# andres-rgb-controller-esp8266-12_2021-06.net
KiCad netlist of a schematic drawn in EasyEDA
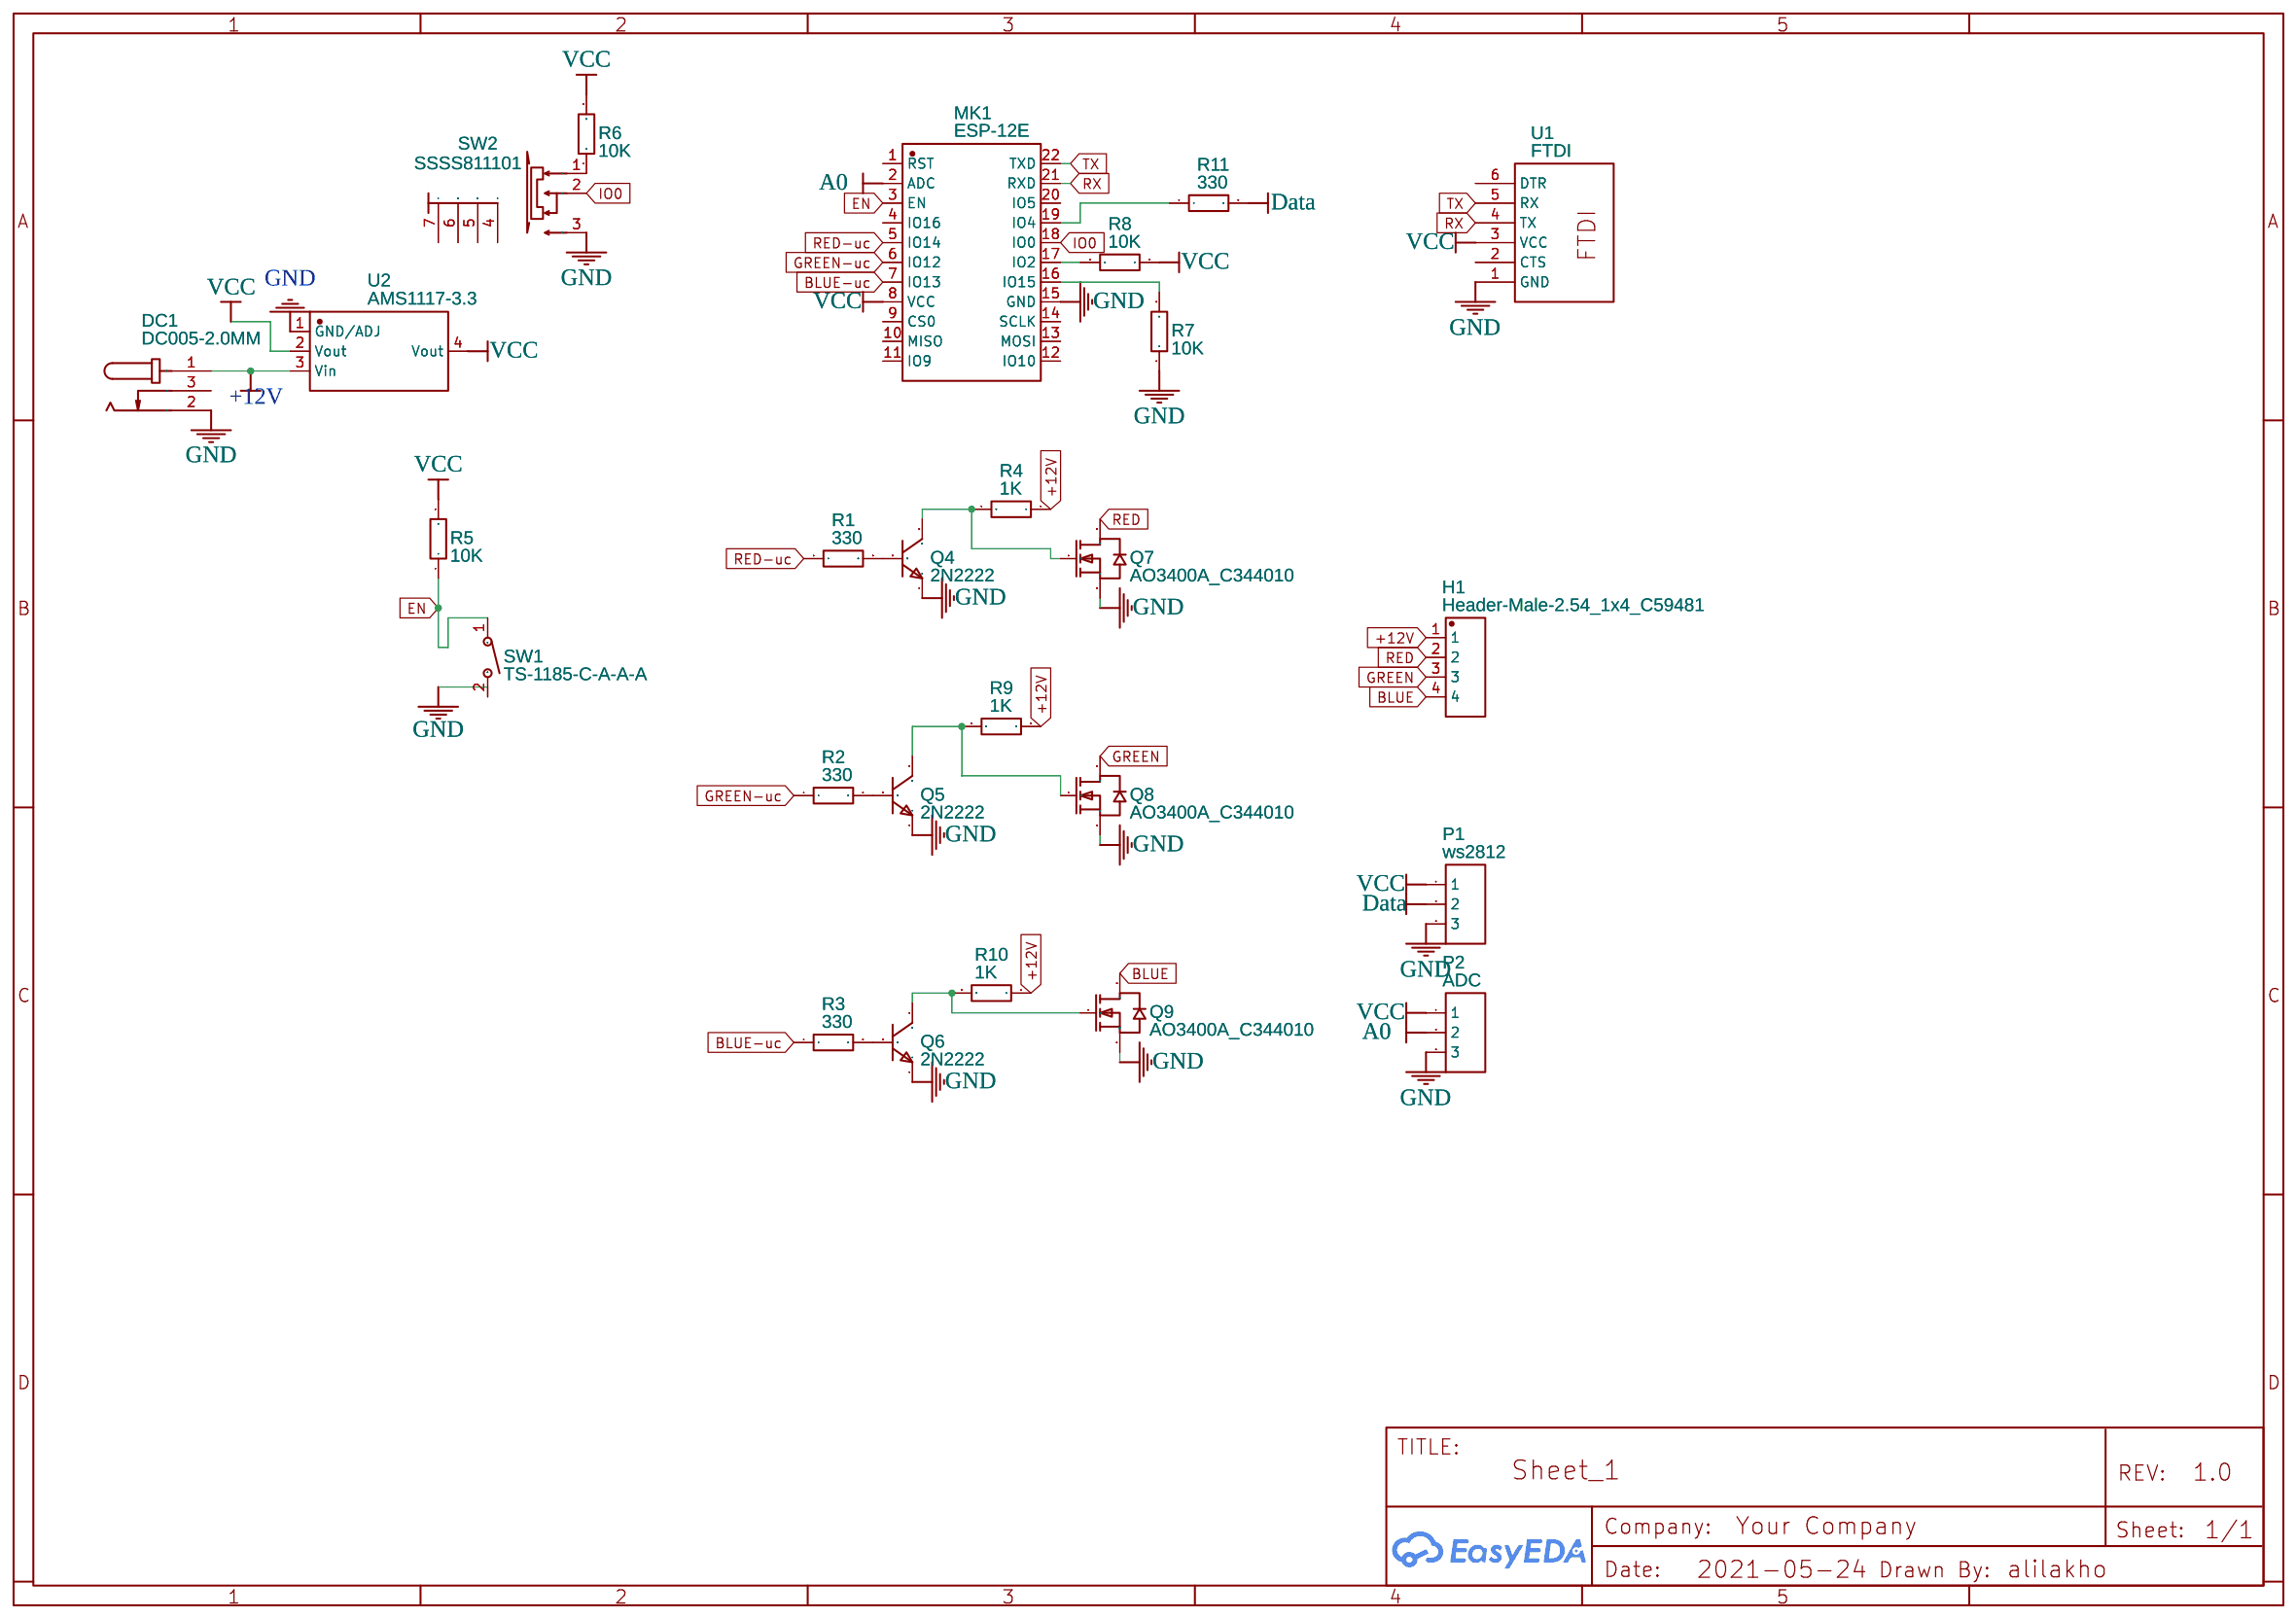
[diagram p0: schematic sheet]

(export (version "E")
  (design (tool "Eeschema 10.0.6"))
  (components
    (comp (ref "DC1")
      (value "DC005-2.0MM")
      (fields (field (name "BOM_Supplier Part") "C111567"))
      (libsource (lib "") (part "DC005-2.0MM"))
    )
    (comp (ref "H1")
      (value "Header-Male-2.54_1x4_C59481")
      (fields
        (field (name "BOM_Manufacturer Part") "Headers  Pins 1*4P")
        (field (name "BOM_Supplier Part") "C59481")
      )
      (libsource (lib "") (part "Header-Male-2.54_1x4_C59481"))
    )
    (comp (ref "MK1")
      (value "ESP-12E")
      (fields (field (name "BOM_Supplier Part") "C89297"))
      (libsource (lib "") (part "ESP-12E"))
    )
    (comp (ref "P1")
      (value "ws2812")
      (fields
        (field (name "BOM_Manufacturer Part") "Header-Female-2.54_1x3")
        (field (name "BOM_Supplier Part") "C146243")
      )
      (libsource (lib "") (part "Header-Female-2.54_1x3"))
    )
    (comp (ref "P2")
      (value "ADC")
      (fields
        (field (name "BOM_Manufacturer Part") "Header-Female-2.54_1x3")
        (field (name "BOM_Supplier Part") "C146243")
      )
      (libsource (lib "") (part "Header-Female-2.54_1x3"))
    )
    (comp (ref "Q4")
      (value "2N2222")
      (fields (field (name "BOM_Supplier Part") "C118536"))
      (libsource (lib "") (part "2N2222"))
    )
    (comp (ref "Q5")
      (value "2N2222")
      (fields (field (name "BOM_Supplier Part") "C118536"))
      (libsource (lib "") (part "2N2222"))
    )
    (comp (ref "Q6")
      (value "2N2222")
      (fields (field (name "BOM_Supplier Part") "C118536"))
      (libsource (lib "") (part "2N2222"))
    )
    (comp (ref "Q7")
      (value "AO3400A_C344010")
      (fields (field (name "BOM_Manufacturer Part") "AO3400A") (field (name "BOM_Supplier Part") "C344010"))
      (libsource (lib "") (part "AO3400A_C344010"))
    )
    (comp (ref "Q8")
      (value "AO3400A_C344010")
      (fields (field (name "BOM_Manufacturer Part") "AO3400A") (field (name "BOM_Supplier Part") "C344010"))
      (libsource (lib "") (part "AO3400A_C344010"))
    )
    (comp (ref "Q9")
      (value "AO3400A_C344010")
      (fields (field (name "BOM_Manufacturer Part") "AO3400A") (field (name "BOM_Supplier Part") "C344010"))
      (libsource (lib "") (part "AO3400A_C344010"))
    )
    (comp (ref "R1")
      (value "330")
      (fields
        (field (name "BOM_Manufacturer Part") "0805W8J0331T5E")
        (field (name "BOM_Supplier Part") "C25306")
      )
      (libsource (lib "") (part "0805W8J0331T5E"))
    )
    (comp (ref "R2")
      (value "330")
      (fields
        (field (name "BOM_Manufacturer Part") "0805W8J0331T5E")
        (field (name "BOM_Supplier Part") "C25306")
      )
      (libsource (lib "") (part "0805W8J0331T5E"))
    )
    (comp (ref "R3")
      (value "330")
      (fields
        (field (name "BOM_Manufacturer Part") "0805W8J0331T5E")
        (field (name "BOM_Supplier Part") "C25306")
      )
      (libsource (lib "") (part "0805W8J0331T5E"))
    )
    (comp (ref "R4")
      (value "1K")
      (fields
        (field (name "BOM_Manufacturer Part") "1210W3J0102T5E")
        (field (name "BOM_Supplier Part") "C25681")
      )
      (libsource (lib "") (part "1210W3J0102T5E"))
    )
    (comp (ref "R5")
      (value "10K")
      (fields
        (field (name "BOM_Manufacturer Part") "1206W4F1002T5E")
        (field (name "BOM_Supplier Part") "C17902")
      )
      (libsource (lib "") (part "1206W4F1002T5E_1"))
    )
    (comp (ref "R6")
      (value "10K")
      (fields
        (field (name "BOM_Manufacturer Part") "1206W4F1002T5E")
        (field (name "BOM_Supplier Part") "C17902")
      )
      (libsource (lib "") (part "1206W4F1002T5E_1"))
    )
    (comp (ref "R7")
      (value "10K")
      (fields
        (field (name "BOM_Manufacturer Part") "1206W4F1002T5E")
        (field (name "BOM_Supplier Part") "C17902")
      )
      (libsource (lib "") (part "1206W4F1002T5E_1"))
    )
    (comp (ref "R8")
      (value "10K")
      (fields
        (field (name "BOM_Manufacturer Part") "1206W4F1002T5E")
        (field (name "BOM_Supplier Part") "C17902")
      )
      (libsource (lib "") (part "1206W4F1002T5E"))
    )
    (comp (ref "R9")
      (value "1K")
      (fields
        (field (name "BOM_Manufacturer Part") "1210W3J0102T5E")
        (field (name "BOM_Supplier Part") "C25681")
      )
      (libsource (lib "") (part "1210W3J0102T5E"))
    )
    (comp (ref "R10")
      (value "1K")
      (fields
        (field (name "BOM_Manufacturer Part") "1210W3J0102T5E")
        (field (name "BOM_Supplier Part") "C25681")
      )
      (libsource (lib "") (part "1210W3J0102T5E"))
    )
    (comp (ref "R11")
      (value "330")
      (fields
        (field (name "BOM_Manufacturer Part") "0805W8J0331T5E")
        (field (name "BOM_Supplier Part") "C25306")
      )
      (libsource (lib "") (part "0805W8J0331T5E"))
    )
    (comp (ref "SW1")
      (value "TS-1185-C-A-A-A")
      (fields (field (name "BOM_Supplier Part") "C561518"))
      (libsource (lib "") (part "TS-1185-C-A-A-A"))
    )
    (comp (ref "SW2")
      (value "SSSS811101")
      (fields (field (name "BOM_Supplier Part") "C109335"))
      (libsource (lib "") (part "SSSS811101"))
    )
    (comp (ref "U1") (value "FTDI") (libsource (lib "") (part "FTDI")))
    (comp (ref "U2")
      (value "AMS1117-3.3")
      (fields (field (name "BOM_Supplier Part") "C6186"))
      (libsource (lib "") (part "AMS1117-3.3"))
    )
  )
  (nets
    (net (code "1") (name "+12V") (class "Default")
      (node (ref "DC1") (pin "1") (pinfunction "1_1") (pintype "unspecified"))
      (node (ref "H1") (pin "1") (pinfunction "1_1") (pintype "unspecified"))
      (node (ref "R10") (pin "1") (pinfunction "1_1") (pintype "input"))
      (node (ref "R4") (pin "1") (pinfunction "1_1") (pintype "input"))
      (node (ref "R9") (pin "1") (pinfunction "1_1") (pintype "input"))
      (node (ref "U2") (pin "3") (pinfunction "Vin_3") (pintype "unspecified"))
    )
    (net (code "2") (name "A0") (class "Default")
      (node (ref "MK1") (pin "2") (pinfunction "ADC_2") (pintype "unspecified"))
      (node (ref "P2") (pin "2") (pinfunction "2_2") (pintype "input"))
    )
    (net (code "3") (name "BLUE") (class "Default")
      (node (ref "H1") (pin "4") (pinfunction "4_4") (pintype "unspecified"))
      (node (ref "Q9") (pin "3") (pinfunction "D_3") (pintype "unspecified"))
    )
    (net (code "4") (name "BLUE-uc") (class "Default")
      (node (ref "MK1") (pin "7") (pinfunction "IO13_7") (pintype "unspecified"))
      (node (ref "R3") (pin "1") (pinfunction "1_1") (pintype "input"))
    )
    (net (code "5") (name "Data") (class "Default")
      (node (ref "P1") (pin "2") (pinfunction "2_2") (pintype "input"))
      (node (ref "R11") (pin "2") (pinfunction "2_2") (pintype "input"))
    )
    (net (code "6") (name "EN") (class "Default")
      (node (ref "MK1") (pin "3") (pinfunction "EN_3") (pintype "unspecified"))
      (node (ref "R5") (pin "1") (pinfunction "1_1") (pintype "input"))
      (node (ref "SW1") (pin "1") (pinfunction "1_1") (pintype "unspecified"))
    )
    (net (code "7") (name "GND") (class "Default")
      (node (ref "DC1") (pin "2") (pinfunction "2_2") (pintype "unspecified"))
      (node (ref "MK1") (pin "15") (pinfunction "GND_15") (pintype "unspecified"))
      (node (ref "P1") (pin "3") (pinfunction "3_3") (pintype "input"))
      (node (ref "P2") (pin "3") (pinfunction "3_3") (pintype "input"))
      (node (ref "Q4") (pin "1") (pinfunction "E_1") (pintype "unspecified"))
      (node (ref "Q5") (pin "1") (pinfunction "E_1") (pintype "unspecified"))
      (node (ref "Q6") (pin "1") (pinfunction "E_1") (pintype "unspecified"))
      (node (ref "Q7") (pin "2") (pinfunction "S_2") (pintype "unspecified"))
      (node (ref "Q8") (pin "2") (pinfunction "S_2") (pintype "unspecified"))
      (node (ref "Q9") (pin "2") (pinfunction "S_2") (pintype "unspecified"))
      (node (ref "R7") (pin "1") (pinfunction "1_1") (pintype "input"))
      (node (ref "SW1") (pin "2") (pinfunction "2_2") (pintype "unspecified"))
      (node (ref "SW2") (pin "3") (pinfunction "3_3") (pintype "unspecified"))
      (node (ref "U1") (pin "1") (pinfunction "GND_1") (pintype "unspecified"))
      (node (ref "U2") (pin "1") (pinfunction "GND/ADJ_1") (pintype "unspecified"))
    )
    (net (code "8") (name "GREEN") (class "Default")
      (node (ref "H1") (pin "3") (pinfunction "3_3") (pintype "unspecified"))
      (node (ref "Q8") (pin "3") (pinfunction "D_3") (pintype "unspecified"))
    )
    (net (code "9") (name "GREEN-uc") (class "Default")
      (node (ref "MK1") (pin "6") (pinfunction "IO12_6") (pintype "unspecified"))
      (node (ref "R2") (pin "1") (pinfunction "1_1") (pintype "input"))
    )
    (net (code "10") (name "IO0") (class "Default")
      (node (ref "MK1") (pin "18") (pinfunction "IO0_18") (pintype "unspecified"))
      (node (ref "SW2") (pin "2") (pinfunction "2_2") (pintype "unspecified"))
    )
    (net (code "11") (name "Net-(MK1-IO2)") (class "Default")
      (node (ref "MK1") (pin "17") (pinfunction "IO2_17") (pintype "unspecified"))
      (node (ref "R8") (pin "2") (pinfunction "2_2") (pintype "input"))
    )
    (net (code "12") (name "Net-(MK1-IO4)") (class "Default")
      (node (ref "MK1") (pin "19") (pinfunction "IO4_19") (pintype "unspecified"))
      (node (ref "R11") (pin "1") (pinfunction "1_1") (pintype "input"))
    )
    (net (code "13") (name "Net-(MK1-IO15)") (class "Default")
      (node (ref "MK1") (pin "16") (pinfunction "IO15_16") (pintype "unspecified"))
      (node (ref "R7") (pin "2") (pinfunction "2_2") (pintype "input"))
    )
    (net (code "14") (name "Net-(Q4-B)") (class "Default")
      (node (ref "Q4") (pin "2") (pinfunction "B_2") (pintype "unspecified"))
      (node (ref "R1") (pin "2") (pinfunction "2_2") (pintype "input"))
    )
    (net (code "15") (name "Net-(Q4-C)") (class "Default")
      (node (ref "Q4") (pin "3") (pinfunction "C_3") (pintype "unspecified"))
      (node (ref "Q7") (pin "1") (pinfunction "G_1") (pintype "unspecified"))
      (node (ref "R4") (pin "2") (pinfunction "2_2") (pintype "input"))
    )
    (net (code "16") (name "Net-(Q5-B)") (class "Default")
      (node (ref "Q5") (pin "2") (pinfunction "B_2") (pintype "unspecified"))
      (node (ref "R2") (pin "2") (pinfunction "2_2") (pintype "input"))
    )
    (net (code "17") (name "Net-(Q5-C)") (class "Default")
      (node (ref "Q5") (pin "3") (pinfunction "C_3") (pintype "unspecified"))
      (node (ref "Q8") (pin "1") (pinfunction "G_1") (pintype "unspecified"))
      (node (ref "R9") (pin "2") (pinfunction "2_2") (pintype "input"))
    )
    (net (code "18") (name "Net-(Q6-B)") (class "Default")
      (node (ref "Q6") (pin "2") (pinfunction "B_2") (pintype "unspecified"))
      (node (ref "R3") (pin "2") (pinfunction "2_2") (pintype "input"))
    )
    (net (code "19") (name "Net-(Q6-C)") (class "Default")
      (node (ref "Q6") (pin "3") (pinfunction "C_3") (pintype "unspecified"))
      (node (ref "Q9") (pin "1") (pinfunction "G_1") (pintype "unspecified"))
      (node (ref "R10") (pin "2") (pinfunction "2_2") (pintype "input"))
    )
    (net (code "20") (name "Net-(R6-Pad1)") (class "Default")
      (node (ref "R6") (pin "1") (pinfunction "1_1") (pintype "input"))
      (node (ref "SW2") (pin "1") (pinfunction "1_1") (pintype "unspecified"))
    )
    (net (code "21") (name "RED") (class "Default")
      (node (ref "H1") (pin "2") (pinfunction "2_2") (pintype "unspecified"))
      (node (ref "Q7") (pin "3") (pinfunction "D_3") (pintype "unspecified"))
    )
    (net (code "22") (name "RED-uc") (class "Default")
      (node (ref "MK1") (pin "5") (pinfunction "IO14_5") (pintype "unspecified"))
      (node (ref "R1") (pin "1") (pinfunction "1_1") (pintype "input"))
    )
    (net (code "23") (name "RX") (class "Default")
      (node (ref "MK1") (pin "21") (pinfunction "RXD_21") (pintype "unspecified"))
      (node (ref "U1") (pin "4") (pinfunction "TX_4") (pintype "unspecified"))
    )
    (net (code "24") (name "TX") (class "Default")
      (node (ref "MK1") (pin "22") (pinfunction "TXD_22") (pintype "unspecified"))
      (node (ref "U1") (pin "5") (pinfunction "RX_5") (pintype "unspecified"))
    )
    (net (code "25") (name "VCC") (class "Default")
      (node (ref "MK1") (pin "8") (pinfunction "VCC_8") (pintype "unspecified"))
      (node (ref "P1") (pin "1") (pinfunction "1_1") (pintype "input"))
      (node (ref "P2") (pin "1") (pinfunction "1_1") (pintype "input"))
      (node (ref "R5") (pin "2") (pinfunction "2_2") (pintype "input"))
      (node (ref "R6") (pin "2") (pinfunction "2_2") (pintype "input"))
      (node (ref "R8") (pin "1") (pinfunction "1_1") (pintype "input"))
      (node (ref "U1") (pin "3") (pinfunction "VCC_3") (pintype "unspecified"))
      (node (ref "U2") (pin "2") (pinfunction "Vout_2") (pintype "unspecified"))
      (node (ref "U2") (pin "4") (pinfunction "Vout_4") (pintype "unspecified"))
    )
    (net (code "26") (name "unconnected-(DC1-Pad3)") (class "Default")
      (node (ref "DC1") (pin "3") (pinfunction "3_3") (pintype "unspecified"))
    )
    (net (code "27") (name "unconnected-(MK1-CS0-Pad9)") (class "Default")
      (node (ref "MK1") (pin "9") (pinfunction "CS0_9") (pintype "unspecified"))
    )
    (net (code "28") (name "unconnected-(MK1-IO5-Pad20)") (class "Default")
      (node (ref "MK1") (pin "20") (pinfunction "IO5_20") (pintype "unspecified"))
    )
    (net (code "29") (name "unconnected-(MK1-IO9-Pad11)") (class "Default")
      (node (ref "MK1") (pin "11") (pinfunction "IO9_11") (pintype "unspecified"))
    )
    (net (code "30") (name "unconnected-(MK1-IO10-Pad12)") (class "Default")
      (node (ref "MK1") (pin "12") (pinfunction "IO10_12") (pintype "unspecified"))
    )
    (net (code "31") (name "unconnected-(MK1-IO16-Pad4)") (class "Default")
      (node (ref "MK1") (pin "4") (pinfunction "IO16_4") (pintype "unspecified"))
    )
    (net (code "32") (name "unconnected-(MK1-MISO-Pad10)") (class "Default")
      (node (ref "MK1") (pin "10") (pinfunction "MISO_10") (pintype "unspecified"))
    )
    (net (code "33") (name "unconnected-(MK1-MOSI-Pad13)") (class "Default")
      (node (ref "MK1") (pin "13") (pinfunction "MOSI_13") (pintype "unspecified"))
    )
    (net (code "34") (name "unconnected-(MK1-RST-Pad1)") (class "Default")
      (node (ref "MK1") (pin "1") (pinfunction "RST_1") (pintype "unspecified"))
    )
    (net (code "35") (name "unconnected-(MK1-SCLK-Pad14)") (class "Default")
      (node (ref "MK1") (pin "14") (pinfunction "SCLK_14") (pintype "unspecified"))
    )
    (net (code "36") (name "unconnected-(SW2-Pad4)") (class "Default")
      (node (ref "SW2") (pin "4") (pinfunction "4_4") (pintype "unspecified"))
    )
    (net (code "37") (name "unconnected-(SW2-Pad5)") (class "Default")
      (node (ref "SW2") (pin "5") (pinfunction "5_5") (pintype "unspecified"))
    )
    (net (code "38") (name "unconnected-(SW2-Pad6)") (class "Default")
      (node (ref "SW2") (pin "6") (pinfunction "6_6") (pintype "unspecified"))
    )
    (net (code "39") (name "unconnected-(SW2-Pad7)") (class "Default")
      (node (ref "SW2") (pin "7") (pinfunction "7_7") (pintype "unspecified"))
    )
    (net (code "40") (name "unconnected-(U1-CTS-Pad2)") (class "Default")
      (node (ref "U1") (pin "2") (pinfunction "CTS_2") (pintype "unspecified"))
    )
    (net (code "41") (name "unconnected-(U1-DTR-Pad6)") (class "Default")
      (node (ref "U1") (pin "6") (pinfunction "DTR_6") (pintype "unspecified"))
    )
  )
)
